# SCH_touchsensor_mic_2024-07-11.net
KiCad netlist of a schematic drawn in EasyEDA
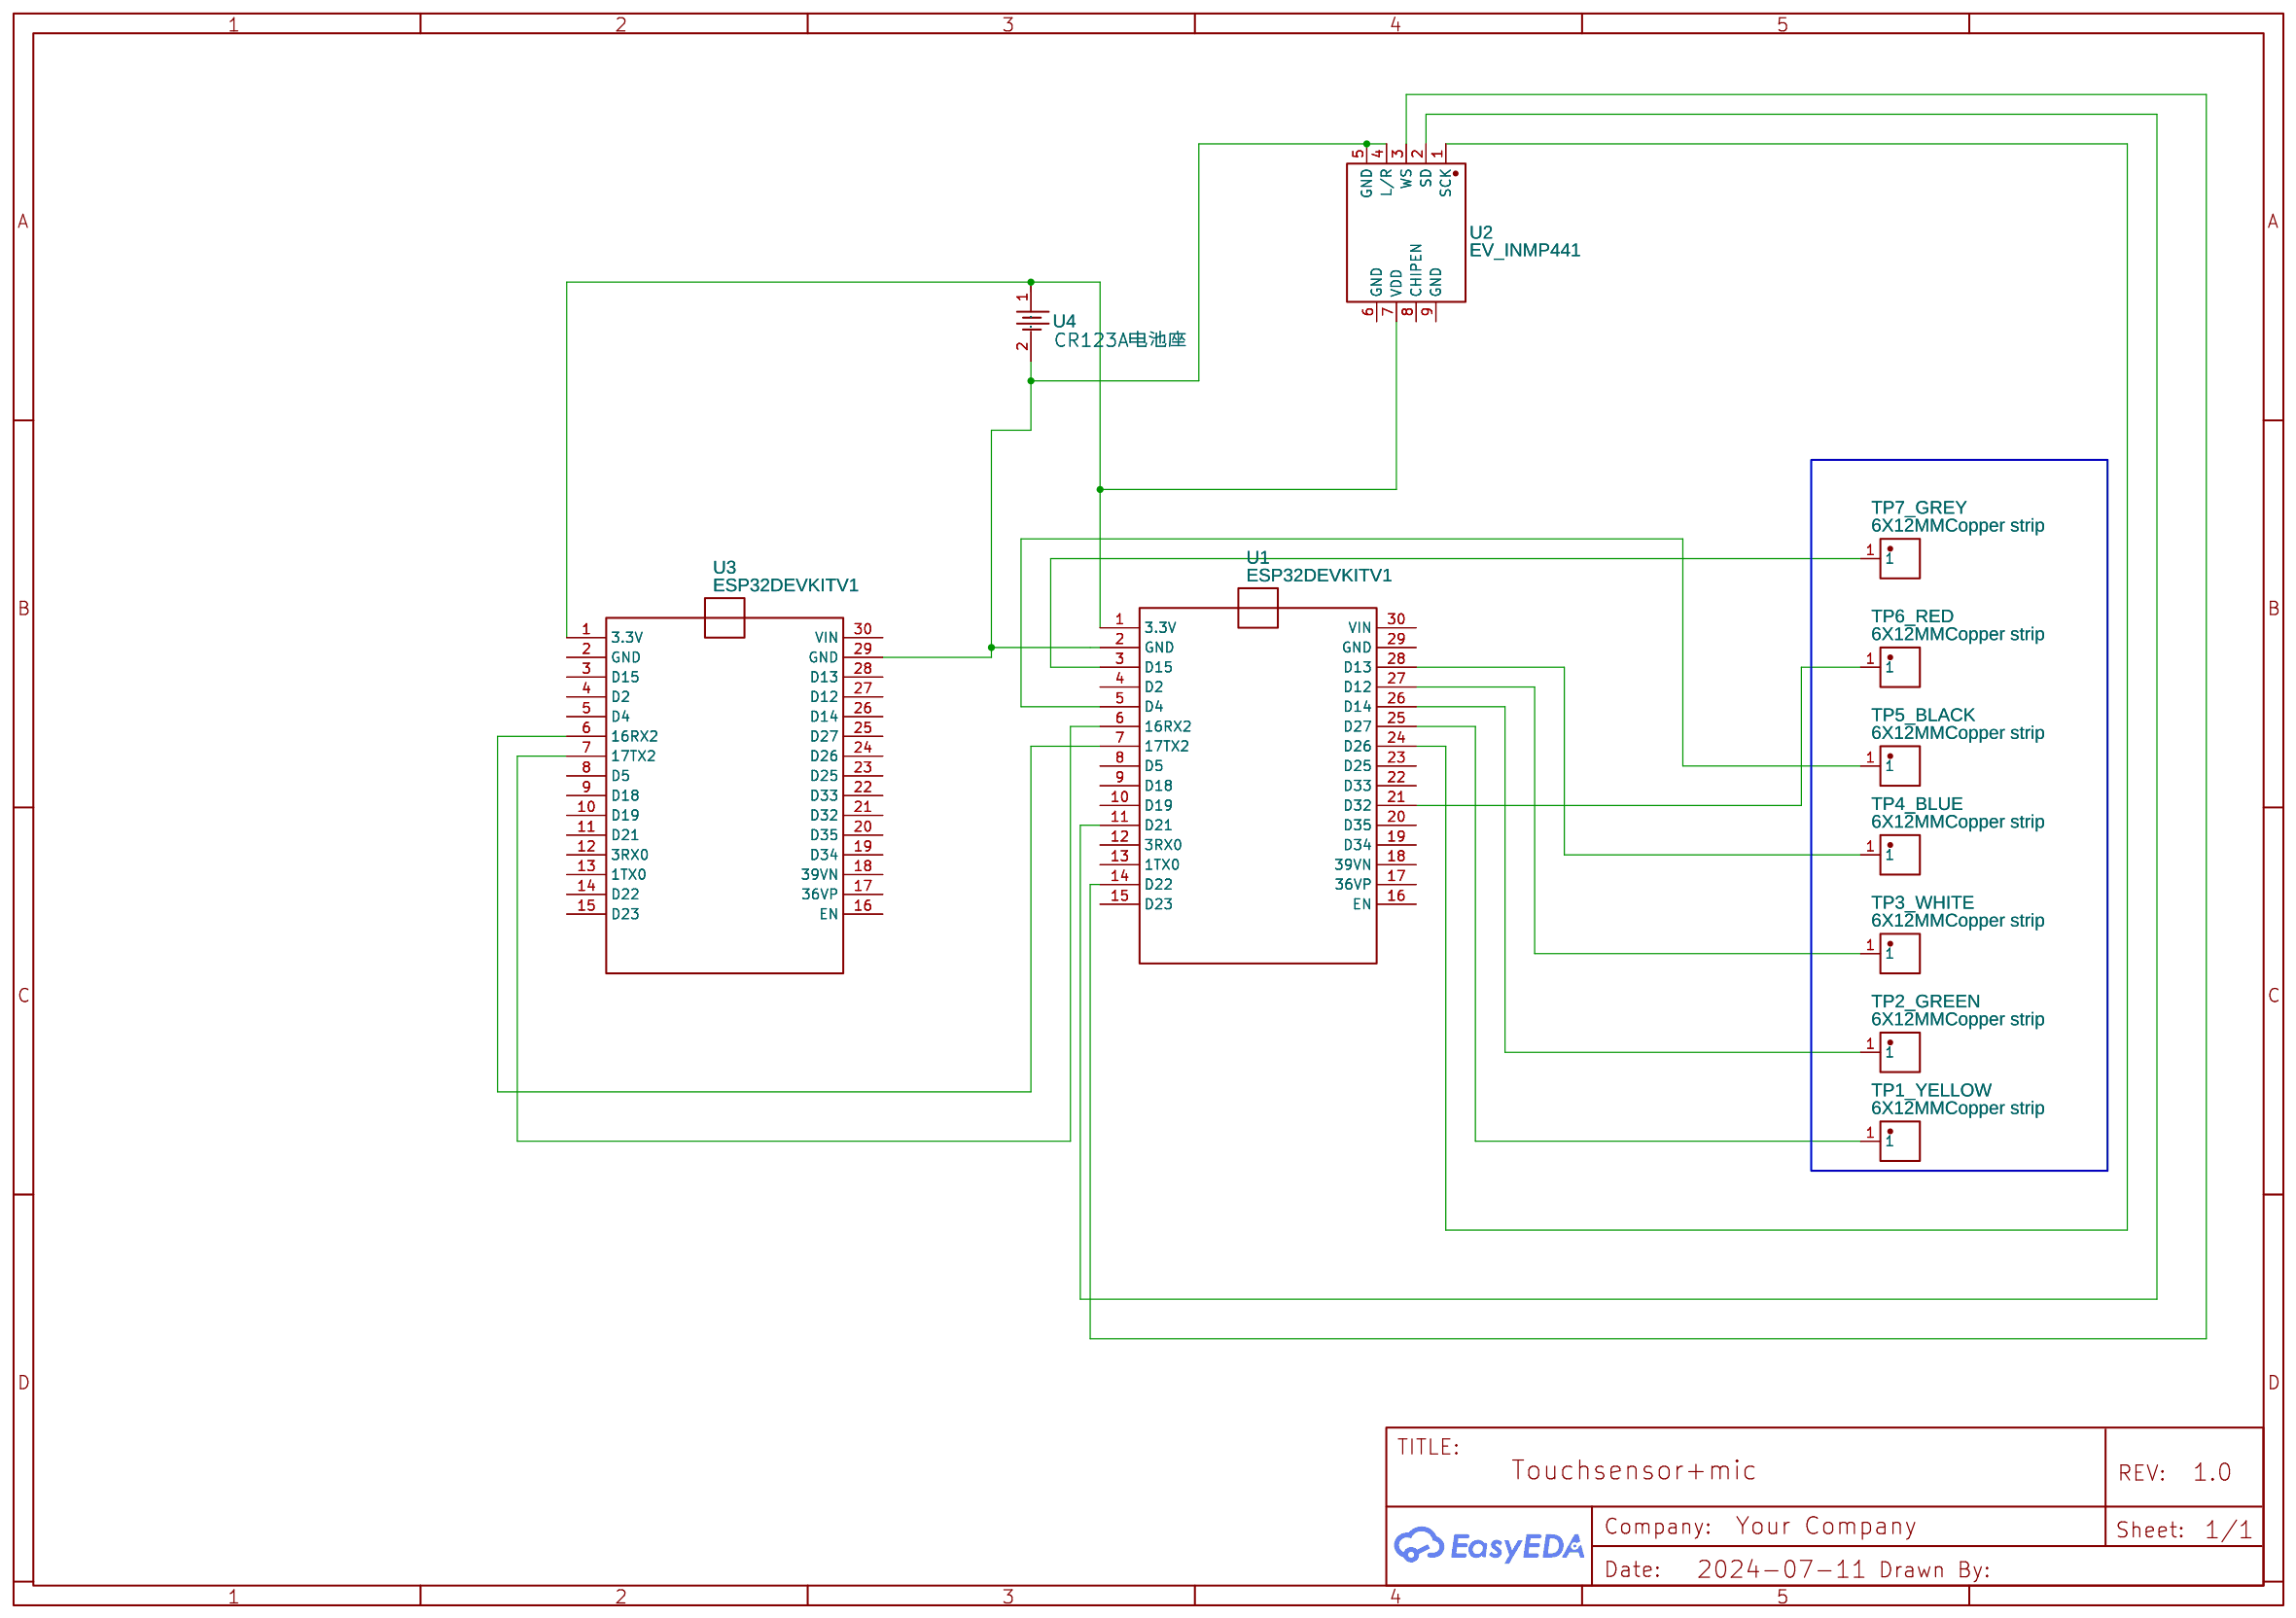
[diagram p0: schematic sheet]

(export (version "E")
  (design (tool "Eeschema 10.0.6"))
  (components
    (comp (ref "TP1_YELLOW")
      (value "6X12MMCopper strip")
      (fields (field (name "Manufacturer Part") "6X12mm铜片"))
      (libsource (lib "") (part "6X12MMCopper strip"))
    )
    (comp (ref "TP2_GREEN")
      (value "6X12MMCopper strip")
      (fields (field (name "Manufacturer Part") "6X12mm铜片"))
      (libsource (lib "") (part "6X12MMCopper strip_5"))
    )
    (comp (ref "TP3_WHITE")
      (value "6X12MMCopper strip")
      (fields (field (name "Manufacturer Part") "6X12mm铜片"))
      (libsource (lib "") (part "6X12MMCopper strip_6"))
    )
    (comp (ref "TP4_BLUE")
      (value "6X12MMCopper strip")
      (fields (field (name "Manufacturer Part") "6X12mm铜片"))
      (libsource (lib "") (part "6X12MMCopper strip_3"))
    )
    (comp (ref "TP5_BLACK")
      (value "6X12MMCopper strip")
      (fields (field (name "Manufacturer Part") "6X12mm铜片"))
      (libsource (lib "") (part "6X12MMCopper strip_2"))
    )
    (comp (ref "TP6_RED")
      (value "6X12MMCopper strip")
      (fields (field (name "Manufacturer Part") "6X12mm铜片"))
      (libsource (lib "") (part "6X12MMCopper strip_4"))
    )
    (comp (ref "TP7_GREY")
      (value "6X12MMCopper strip")
      (fields (field (name "Manufacturer Part") "6X12mm铜片"))
      (libsource (lib "") (part "6X12MMCopper strip_1"))
    )
    (comp (ref "U1") (value "ESP32DEVKITV1") (libsource (lib "") (part "ESP32DEVKITV1")))
    (comp (ref "U2")
      (value "EV_INMP441")
      (fields (field (name "Manufacturer") "TDK InvenSense(应美盛)"))
      (libsource (lib "") (part "EV_INMP441"))
    )
    (comp (ref "U3") (value "ESP32DEVKITV1") (libsource (lib "") (part "ESP32DEVKITV1")))
    (comp (ref "U4") (value "CR123A电池座") (libsource (lib "") (part "CR123A电池座")))
  )
  (nets
    (net (code "1") (name "Net-(U1-3.3V)") (class "Default")
      (node (ref "U1") (pin "1") (pinfunction "3.3V_1") (pintype "unspecified"))
      (node (ref "U2") (pin "7") (pinfunction "VDD_7") (pintype "unspecified"))
      (node (ref "U3") (pin "1") (pinfunction "3.3V_1") (pintype "unspecified"))
      (node (ref "U4") (pin "1") (pinfunction "1_1") (pintype "input"))
    )
    (net (code "2") (name "Net-(U1-16RX2)") (class "Default")
      (node (ref "U1") (pin "6") (pinfunction "16RX2_6") (pintype "unspecified"))
      (node (ref "U3") (pin "7") (pinfunction "17TX2_7") (pintype "unspecified"))
    )
    (net (code "3") (name "Net-(U1-17TX2)") (class "Default")
      (node (ref "U1") (pin "7") (pinfunction "17TX2_7") (pintype "unspecified"))
      (node (ref "U3") (pin "6") (pinfunction "16RX2_6") (pintype "unspecified"))
    )
    (net (code "4") (name "Net-(U1-D4)") (class "Default")
      (node (ref "TP5_BLACK") (pin "1") (pinfunction "1_1") (pintype "unspecified"))
      (node (ref "U1") (pin "5") (pinfunction "D4_5") (pintype "unspecified"))
    )
    (net (code "5") (name "Net-(U1-D12)") (class "Default")
      (node (ref "TP3_WHITE") (pin "1") (pinfunction "1_1") (pintype "unspecified"))
      (node (ref "U1") (pin "27") (pinfunction "D12_27") (pintype "unspecified"))
    )
    (net (code "6") (name "Net-(U1-D13)") (class "Default")
      (node (ref "TP4_BLUE") (pin "1") (pinfunction "1_1") (pintype "unspecified"))
      (node (ref "U1") (pin "28") (pinfunction "D13_28") (pintype "unspecified"))
    )
    (net (code "7") (name "Net-(U1-D14)") (class "Default")
      (node (ref "TP2_GREEN") (pin "1") (pinfunction "1_1") (pintype "unspecified"))
      (node (ref "U1") (pin "26") (pinfunction "D14_26") (pintype "unspecified"))
    )
    (net (code "8") (name "Net-(U1-D15)") (class "Default")
      (node (ref "TP7_GREY") (pin "1") (pinfunction "1_1") (pintype "unspecified"))
      (node (ref "U1") (pin "3") (pinfunction "D15_3") (pintype "unspecified"))
    )
    (net (code "9") (name "Net-(U1-D21)") (class "Default")
      (node (ref "U1") (pin "11") (pinfunction "D21_11") (pintype "unspecified"))
      (node (ref "U2") (pin "2") (pinfunction "SD_2") (pintype "unspecified"))
    )
    (net (code "10") (name "Net-(U1-D22)") (class "Default")
      (node (ref "U1") (pin "14") (pinfunction "D22_14") (pintype "unspecified"))
      (node (ref "U2") (pin "3") (pinfunction "WS_3") (pintype "unspecified"))
    )
    (net (code "11") (name "Net-(U1-D26)") (class "Default")
      (node (ref "U1") (pin "24") (pinfunction "D26_24") (pintype "unspecified"))
      (node (ref "U2") (pin "1") (pinfunction "SCK_1") (pintype "unspecified"))
    )
    (net (code "12") (name "Net-(U1-D27)") (class "Default")
      (node (ref "TP1_YELLOW") (pin "1") (pinfunction "1_1") (pintype "unspecified"))
      (node (ref "U1") (pin "25") (pinfunction "D27_25") (pintype "unspecified"))
    )
    (net (code "13") (name "Net-(U1-D32)") (class "Default")
      (node (ref "TP6_RED") (pin "1") (pinfunction "1_1") (pintype "unspecified"))
      (node (ref "U1") (pin "21") (pinfunction "D32_21") (pintype "unspecified"))
    )
    (net (code "14") (name "Net-(U2-L{slash}R)") (class "Default")
      (node (ref "U1") (pin "2") (pinfunction "GND_2") (pintype "unspecified"))
      (node (ref "U2") (pin "4") (pinfunction "L/R_4") (pintype "unspecified"))
      (node (ref "U2") (pin "5") (pinfunction "GND_5") (pintype "unspecified"))
      (node (ref "U3") (pin "29") (pinfunction "GND_29") (pintype "unspecified"))
      (node (ref "U4") (pin "2") (pinfunction "2_2") (pintype "input"))
    )
    (net (code "15") (name "unconnected-(U1-1TX0-Pad13)") (class "Default")
      (node (ref "U1") (pin "13") (pinfunction "1TX0_13") (pintype "unspecified"))
    )
    (net (code "16") (name "unconnected-(U1-3RX0-Pad12)") (class "Default")
      (node (ref "U1") (pin "12") (pinfunction "3RX0_12") (pintype "unspecified"))
    )
    (net (code "17") (name "unconnected-(U1-36VP-Pad17)") (class "Default")
      (node (ref "U1") (pin "17") (pinfunction "36VP_17") (pintype "unspecified"))
    )
    (net (code "18") (name "unconnected-(U1-39VN-Pad18)") (class "Default")
      (node (ref "U1") (pin "18") (pinfunction "39VN_18") (pintype "unspecified"))
    )
    (net (code "19") (name "unconnected-(U1-D2-Pad4)") (class "Default")
      (node (ref "U1") (pin "4") (pinfunction "D2_4") (pintype "unspecified"))
    )
    (net (code "20") (name "unconnected-(U1-D5-Pad8)") (class "Default")
      (node (ref "U1") (pin "8") (pinfunction "D5_8") (pintype "unspecified"))
    )
    (net (code "21") (name "unconnected-(U1-D18-Pad9)") (class "Default")
      (node (ref "U1") (pin "9") (pinfunction "D18_9") (pintype "unspecified"))
    )
    (net (code "22") (name "unconnected-(U1-D19-Pad10)") (class "Default")
      (node (ref "U1") (pin "10") (pinfunction "D19_10") (pintype "unspecified"))
    )
    (net (code "23") (name "unconnected-(U1-D23-Pad15)") (class "Default")
      (node (ref "U1") (pin "15") (pinfunction "D23_15") (pintype "unspecified"))
    )
    (net (code "24") (name "unconnected-(U1-D25-Pad23)") (class "Default")
      (node (ref "U1") (pin "23") (pinfunction "D25_23") (pintype "unspecified"))
    )
    (net (code "25") (name "unconnected-(U1-D33-Pad22)") (class "Default")
      (node (ref "U1") (pin "22") (pinfunction "D33_22") (pintype "unspecified"))
    )
    (net (code "26") (name "unconnected-(U1-D34-Pad19)") (class "Default")
      (node (ref "U1") (pin "19") (pinfunction "D34_19") (pintype "unspecified"))
    )
    (net (code "27") (name "unconnected-(U1-D35-Pad20)") (class "Default")
      (node (ref "U1") (pin "20") (pinfunction "D35_20") (pintype "unspecified"))
    )
    (net (code "28") (name "unconnected-(U1-EN-Pad16)") (class "Default")
      (node (ref "U1") (pin "16") (pinfunction "EN_16") (pintype "unspecified"))
    )
    (net (code "29") (name "unconnected-(U1-GND-Pad29)") (class "Default")
      (node (ref "U1") (pin "29") (pinfunction "GND_29") (pintype "unspecified"))
    )
    (net (code "30") (name "unconnected-(U1-VIN-Pad30)") (class "Default")
      (node (ref "U1") (pin "30") (pinfunction "VIN_30") (pintype "unspecified"))
    )
    (net (code "31") (name "unconnected-(U2-CHIPEN-Pad8)") (class "Default")
      (node (ref "U2") (pin "8") (pinfunction "CHIPEN_8") (pintype "unspecified"))
    )
    (net (code "32") (name "unconnected-(U2-GND-Pad6)") (class "Default")
      (node (ref "U2") (pin "6") (pinfunction "GND_6") (pintype "unspecified"))
    )
    (net (code "33") (name "unconnected-(U2-GND-Pad9)") (class "Default")
      (node (ref "U2") (pin "9") (pinfunction "GND_9") (pintype "unspecified"))
    )
    (net (code "34") (name "unconnected-(U3-1TX0-Pad13)") (class "Default")
      (node (ref "U3") (pin "13") (pinfunction "1TX0_13") (pintype "unspecified"))
    )
    (net (code "35") (name "unconnected-(U3-3RX0-Pad12)") (class "Default")
      (node (ref "U3") (pin "12") (pinfunction "3RX0_12") (pintype "unspecified"))
    )
    (net (code "36") (name "unconnected-(U3-36VP-Pad17)") (class "Default")
      (node (ref "U3") (pin "17") (pinfunction "36VP_17") (pintype "unspecified"))
    )
    (net (code "37") (name "unconnected-(U3-39VN-Pad18)") (class "Default")
      (node (ref "U3") (pin "18") (pinfunction "39VN_18") (pintype "unspecified"))
    )
    (net (code "38") (name "unconnected-(U3-D2-Pad4)") (class "Default")
      (node (ref "U3") (pin "4") (pinfunction "D2_4") (pintype "unspecified"))
    )
    (net (code "39") (name "unconnected-(U3-D4-Pad5)") (class "Default")
      (node (ref "U3") (pin "5") (pinfunction "D4_5") (pintype "unspecified"))
    )
    (net (code "40") (name "unconnected-(U3-D5-Pad8)") (class "Default")
      (node (ref "U3") (pin "8") (pinfunction "D5_8") (pintype "unspecified"))
    )
    (net (code "41") (name "unconnected-(U3-D12-Pad27)") (class "Default")
      (node (ref "U3") (pin "27") (pinfunction "D12_27") (pintype "unspecified"))
    )
    (net (code "42") (name "unconnected-(U3-D13-Pad28)") (class "Default")
      (node (ref "U3") (pin "28") (pinfunction "D13_28") (pintype "unspecified"))
    )
    (net (code "43") (name "unconnected-(U3-D14-Pad26)") (class "Default")
      (node (ref "U3") (pin "26") (pinfunction "D14_26") (pintype "unspecified"))
    )
    (net (code "44") (name "unconnected-(U3-D15-Pad3)") (class "Default")
      (node (ref "U3") (pin "3") (pinfunction "D15_3") (pintype "unspecified"))
    )
    (net (code "45") (name "unconnected-(U3-D18-Pad9)") (class "Default")
      (node (ref "U3") (pin "9") (pinfunction "D18_9") (pintype "unspecified"))
    )
    (net (code "46") (name "unconnected-(U3-D19-Pad10)") (class "Default")
      (node (ref "U3") (pin "10") (pinfunction "D19_10") (pintype "unspecified"))
    )
    (net (code "47") (name "unconnected-(U3-D21-Pad11)") (class "Default")
      (node (ref "U3") (pin "11") (pinfunction "D21_11") (pintype "unspecified"))
    )
    (net (code "48") (name "unconnected-(U3-D22-Pad14)") (class "Default")
      (node (ref "U3") (pin "14") (pinfunction "D22_14") (pintype "unspecified"))
    )
    (net (code "49") (name "unconnected-(U3-D23-Pad15)") (class "Default")
      (node (ref "U3") (pin "15") (pinfunction "D23_15") (pintype "unspecified"))
    )
    (net (code "50") (name "unconnected-(U3-D25-Pad23)") (class "Default")
      (node (ref "U3") (pin "23") (pinfunction "D25_23") (pintype "unspecified"))
    )
    (net (code "51") (name "unconnected-(U3-D26-Pad24)") (class "Default")
      (node (ref "U3") (pin "24") (pinfunction "D26_24") (pintype "unspecified"))
    )
    (net (code "52") (name "unconnected-(U3-D27-Pad25)") (class "Default")
      (node (ref "U3") (pin "25") (pinfunction "D27_25") (pintype "unspecified"))
    )
    (net (code "53") (name "unconnected-(U3-D32-Pad21)") (class "Default")
      (node (ref "U3") (pin "21") (pinfunction "D32_21") (pintype "unspecified"))
    )
    (net (code "54") (name "unconnected-(U3-D33-Pad22)") (class "Default")
      (node (ref "U3") (pin "22") (pinfunction "D33_22") (pintype "unspecified"))
    )
    (net (code "55") (name "unconnected-(U3-D34-Pad19)") (class "Default")
      (node (ref "U3") (pin "19") (pinfunction "D34_19") (pintype "unspecified"))
    )
    (net (code "56") (name "unconnected-(U3-D35-Pad20)") (class "Default")
      (node (ref "U3") (pin "20") (pinfunction "D35_20") (pintype "unspecified"))
    )
    (net (code "57") (name "unconnected-(U3-EN-Pad16)") (class "Default")
      (node (ref "U3") (pin "16") (pinfunction "EN_16") (pintype "unspecified"))
    )
    (net (code "58") (name "unconnected-(U3-GND-Pad2)") (class "Default")
      (node (ref "U3") (pin "2") (pinfunction "GND_2") (pintype "unspecified"))
    )
    (net (code "59") (name "unconnected-(U3-VIN-Pad30)") (class "Default")
      (node (ref "U3") (pin "30") (pinfunction "VIN_30") (pintype "unspecified"))
    )
  )
)
